# RTC.net
KiCad netlist of a schematic drawn in Altium Designer
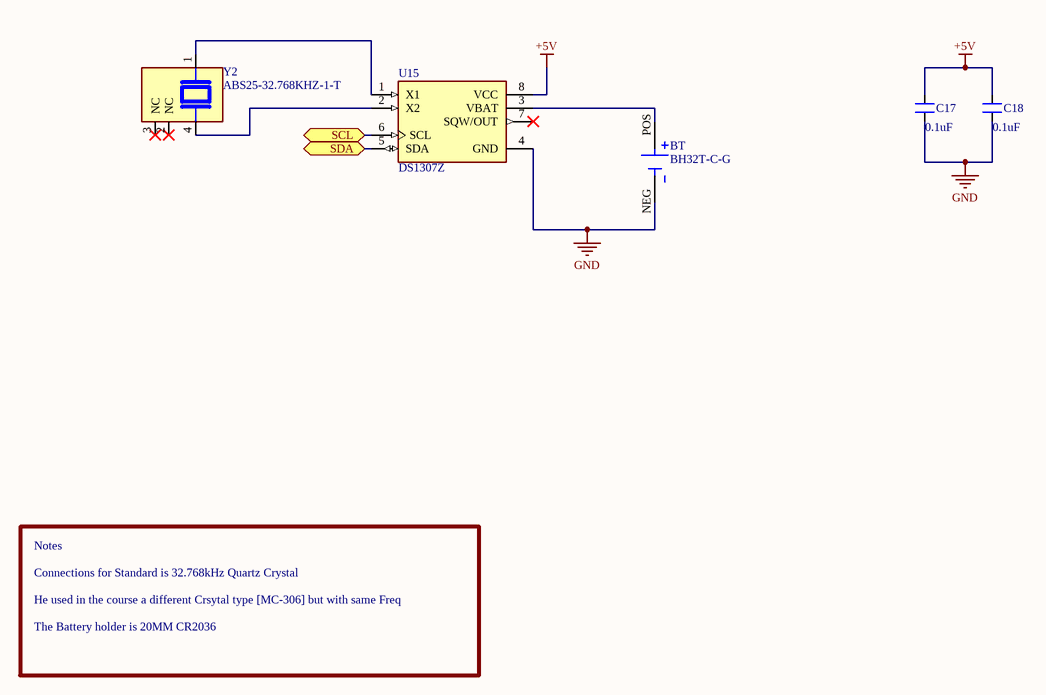
[diagram p0: RTC.SchDoc]

(export (version "E")
  (design (tool "Eeschema 10.0.6"))
  (components
    (comp (ref "BT")
      (value "BH32T-C-G")
      (footprint "BAT_BH32T-C-G")
      (description "BATTERY HOLDER COIN 20MM PC PIN")
      (fields (field (name "MF") "MPD"))
      (libsource (lib "TAREKPCBLIB") (part "BH32T-C-G"))
    )
    (comp (ref "C17")
      (value "0.1uF")
      (footprint "CAP_0805")
      (description "0.1µF ±5% 50V Ceramic Capacitor X7R 0805 (2012 Metric)")
      (fields
        (field (name "MANUFACTURER") "AVX Corporation")
        (field (name "MANUFACTURER PART NUMBER") "08055C104JAT4A")
      )
      (libsource (lib "ESTEEMPCBLIB") (part "CAP_0.1uF-50V-5%-0805"))
    )
    (comp (ref "C18")
      (value "0.1uF")
      (footprint "CAP_0805")
      (description "0.1µF ±5% 50V Ceramic Capacitor X7R 0805 (2012 Metric)")
      (fields
        (field (name "MANUFACTURER") "AVX Corporation")
        (field (name "MANUFACTURER PART NUMBER") "08055C104JAT4A")
      )
      (libsource (lib "ESTEEMPCBLIB") (part "CAP_0.1uF-50V-5%-0805"))
    )
    (comp (ref "U15")
      (value "DS1307Z")
      (footprint "SOIC127P600X175-8N")
      (description "Real Time Clock _RTC_ IC Clock/Calendar 56B IÂ²C, 2-Wire Serial 8-SOIC _0.154, 3.90mm Width_")
      (fields (field (name "MF") "Maxim Integrated"))
      (libsource (lib "TAREKPCBLIB") (part "DS1307Z"))
    )
    (comp (ref "Y2")
      (value "ABS25-32.768KHZ-1-T")
      (footprint "XTAL_ABS25-32.768KHZ-1-T")
      (description "32.768 kHz Â±10ppm Crystal 12.5pF 50 kOhms 4-SOJ, 5.50mm pitch")
      (fields (field (name "MF") "Abracon LLC"))
      (libsource (lib "TAREKPCBLIB") (part "ABS25-32.768KHZ-1-T"))
    )
  )
  (nets
    (net (code "1") (name "+5V") (class "Default")
      (node (ref "C17") (pin "2") (pinfunction "2_2") (pintype "passive"))
      (node (ref "C18") (pin "2") (pinfunction "2_2") (pintype "passive"))
      (node (ref "U15") (pin "8") (pinfunction "VCC_8") (pintype "power_in"))
    )
    (net (code "2") (name "/SCL") (class "Default")
      (node (ref "U15") (pin "6") (pinfunction "SCL_6") (pintype "input"))
    )
    (net (code "3") (name "/SDA") (class "Default")
      (node (ref "U15") (pin "5") (pinfunction "SDA_5") (pintype "bidirectional"))
    )
    (net (code "4") (name "GND") (class "Default")
      (node (ref "BT") (pin "NEG") (pinfunction "NEG_NEG") (pintype "passive"))
      (node (ref "C17") (pin "1") (pinfunction "1_1") (pintype "passive"))
      (node (ref "C18") (pin "1") (pinfunction "1_1") (pintype "passive"))
      (node (ref "U15") (pin "4") (pinfunction "GND_4") (pintype "power_in"))
    )
    (net (code "5") (name "Net-(U15-VBAT)") (class "Default")
      (node (ref "BT") (pin "POS") (pinfunction "POS_POS") (pintype "passive"))
      (node (ref "U15") (pin "3") (pinfunction "VBAT_3") (pintype "power_in"))
    )
    (net (code "6") (name "Net-(U15-X1)") (class "Default")
      (node (ref "U15") (pin "1") (pinfunction "X1_1") (pintype "input"))
      (node (ref "Y2") (pin "1") (pinfunction "1_1") (pintype "passive"))
    )
    (net (code "7") (name "Net-(U15-X2)") (class "Default")
      (node (ref "U15") (pin "2") (pinfunction "X2_2") (pintype "input"))
      (node (ref "Y2") (pin "4") (pinfunction "2_4") (pintype "passive"))
    )
    (net (code "8") (name "unconnected-(U15-SQW{slash}OUT-Pad7)") (class "Default")
      (node (ref "U15") (pin "7") (pinfunction "SQW/OUT_7") (pintype "output+no_connect"))
    )
    (net (code "9") (name "unconnected-(Y2-NC-Pad2)") (class "Default")
      (node (ref "Y2") (pin "2") (pinfunction "NC_2") (pintype "passive+no_connect"))
    )
    (net (code "10") (name "unconnected-(Y2-NC-Pad3)") (class "Default")
      (node (ref "Y2") (pin "3") (pinfunction "NC_3") (pintype "passive+no_connect"))
    )
  )
)
